# stereo-jack.net
KiCad netlist of a schematic drawn in EAGLE
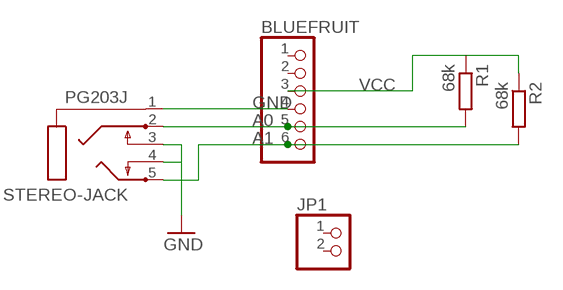
[diagram p0: schematic, sheet 1]

(export (version "E")
  (design (tool "Eeschema 10.0.6"))
  (components
    (comp (ref "BLUEFRUIT")
      (value "PINHD-1X6")
      (footprint "eagle-import:1X06")
      (libsource (lib "eagle-import") (part "PINHD-1X6"))
    )
    (comp (ref "JP1")
      (value "PINHD-1X2")
      (footprint "eagle-import:1X02")
      (libsource (lib "eagle-import") (part "PINHD-1X2"))
    )
    (comp (ref "R1")
      (value "68k")
      (footprint "eagle-import:0207_7")
      (libsource (lib "eagle-import") (part "R-EU_0207/7"))
    )
    (comp (ref "R2")
      (value "68k")
      (footprint "eagle-import:0207_7")
      (libsource (lib "eagle-import") (part "R-EU_0207/7"))
    )
    (comp (ref "STEREO-JACK")
      (value "PG203J")
      (footprint "eagle-import:PG203J")
      (libsource (lib "eagle-import") (part "PG203J"))
    )
  )
  (nets
    (net (code "1") (name "/A0") (class "Default")
      (node (ref "BLUEFRUIT") (pin "5") (pinfunction "5_5") (pintype "passive"))
      (node (ref "R1") (pin "2") (pinfunction "2_2") (pintype "passive"))
      (node (ref "STEREO-JACK") (pin "2") (pinfunction "2_2") (pintype "passive"))
    )
    (net (code "2") (name "/A1") (class "Default")
      (node (ref "BLUEFRUIT") (pin "6") (pinfunction "6_6") (pintype "passive"))
      (node (ref "R2") (pin "2") (pinfunction "2_2") (pintype "passive"))
      (node (ref "STEREO-JACK") (pin "5") (pinfunction "5_5") (pintype "passive"))
    )
    (net (code "3") (name "/VCC") (class "Default")
      (node (ref "BLUEFRUIT") (pin "3") (pinfunction "3_3") (pintype "passive"))
      (node (ref "R1") (pin "1") (pinfunction "1_1") (pintype "passive"))
      (node (ref "R2") (pin "1") (pinfunction "1_1") (pintype "passive"))
    )
    (net (code "4") (name "GND") (class "Default")
      (node (ref "BLUEFRUIT") (pin "4") (pinfunction "4_4") (pintype "passive"))
      (node (ref "STEREO-JACK") (pin "1") (pinfunction "1_1") (pintype "passive"))
      (node (ref "STEREO-JACK") (pin "3") (pinfunction "3_3") (pintype "passive"))
      (node (ref "STEREO-JACK") (pin "4") (pinfunction "4_4") (pintype "passive"))
    )
    (net (code "5") (name "unconnected-(BLUEFRUIT-Pad1)") (class "Default")
      (node (ref "BLUEFRUIT") (pin "1") (pinfunction "1_1") (pintype "passive"))
    )
    (net (code "6") (name "unconnected-(BLUEFRUIT-Pad2)") (class "Default")
      (node (ref "BLUEFRUIT") (pin "2") (pinfunction "2_2") (pintype "passive"))
    )
    (net (code "7") (name "unconnected-(JP1-Pad1)") (class "Default")
      (node (ref "JP1") (pin "1") (pinfunction "1_1") (pintype "passive"))
    )
    (net (code "8") (name "unconnected-(JP1-Pad2)") (class "Default")
      (node (ref "JP1") (pin "2") (pinfunction "2_2") (pintype "passive"))
    )
  )
)
